# IR_Sensor.net
KiCad netlist of a schematic drawn in EAGLE
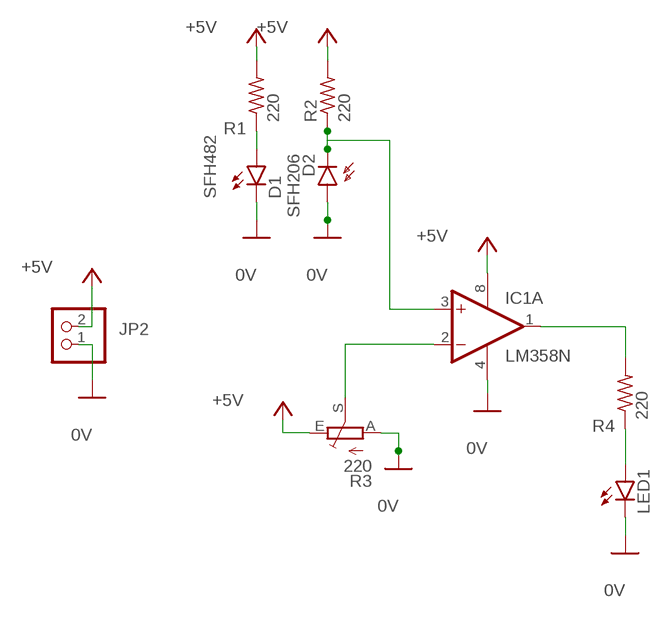
[diagram p0: schematic, sheet 1]

(export (version "E")
  (design (tool "Eeschema 10.0.6"))
  (components
    (comp (ref "D1")
      (value "SFH482")
      (footprint "eagle-import:SFH482")
      (libsource (lib "eagle-import") (part "SFH482"))
    )
    (comp (ref "D2")
      (value "SFH206")
      (footprint "eagle-import:SFH206")
      (fields (field (name "MPN") "SFH206K"))
      (libsource (lib "eagle-import") (part "SFH206"))
    )
    (comp (ref "IC1")
      (value "LM358N")
      (footprint "eagle-import:DIL08")
      (libsource (lib "eagle-import") (part "LM358N"))
    )
    (comp (ref "JP2")
      (value "PINHD-1X2")
      (footprint "eagle-import:1X02")
      (libsource (lib "eagle-import") (part "PINHD-1X2"))
    )
    (comp (ref "LED1")
      (value "LED5MM")
      (footprint "eagle-import:LED5MM")
      (libsource (lib "eagle-import") (part "LED5MM"))
    )
    (comp (ref "R1")
      (value "220")
      (footprint "eagle-import:0207_10")
      (libsource (lib "eagle-import") (part "R-US_0207/10"))
    )
    (comp (ref "R2")
      (value "220")
      (footprint "eagle-import:0207_10")
      (libsource (lib "eagle-import") (part "R-US_0207/10"))
    )
    (comp (ref "R3")
      (value "220")
      (footprint "eagle-import:CA6V")
      (libsource (lib "eagle-import") (part "TRIM_EU-CA6V"))
    )
    (comp (ref "R4")
      (value "220")
      (footprint "eagle-import:0207_10")
      (libsource (lib "eagle-import") (part "R-US_0207/10"))
    )
  )
  (nets
    (net (code "1") (name "+5V") (class "Default")
      (node (ref "IC1") (pin "8") (pinfunction "V+_8") (pintype "power_in"))
      (node (ref "JP2") (pin "2") (pinfunction "2_2") (pintype "passive"))
      (node (ref "R1") (pin "2") (pinfunction "2_2") (pintype "passive"))
      (node (ref "R2") (pin "2") (pinfunction "2_2") (pintype "passive"))
      (node (ref "R3") (pin "E") (pinfunction "E_E") (pintype "passive"))
    )
    (net (code "2") (name "0V") (class "Default")
      (node (ref "D1") (pin "K") (pinfunction "C_K") (pintype "passive"))
      (node (ref "D2") (pin "A") (pinfunction "A_A") (pintype "passive"))
      (node (ref "IC1") (pin "4") (pinfunction "V-_4") (pintype "power_in"))
      (node (ref "JP2") (pin "1") (pinfunction "1_1") (pintype "passive"))
      (node (ref "LED1") (pin "K") (pinfunction "C_K") (pintype "passive"))
      (node (ref "R3") (pin "A") (pinfunction "A_A") (pintype "passive"))
    )
    (net (code "3") (name "Net-(D1-PadA)") (class "Default")
      (node (ref "D1") (pin "A") (pinfunction "A_A") (pintype "passive"))
      (node (ref "R1") (pin "1") (pinfunction "1_1") (pintype "passive"))
    )
    (net (code "4") (name "Net-(D2-C)") (class "Default")
      (node (ref "D2") (pin "K") (pinfunction "C_K") (pintype "passive"))
      (node (ref "IC1") (pin "3") (pinfunction "+IN_3") (pintype "input"))
      (node (ref "R2") (pin "1") (pinfunction "1_1") (pintype "passive"))
    )
    (net (code "5") (name "Net-(IC1A--IN)") (class "Default")
      (node (ref "IC1") (pin "2") (pinfunction "-IN_2") (pintype "input"))
      (node (ref "R3") (pin "S") (pinfunction "S_S") (pintype "passive"))
    )
    (net (code "6") (name "Net-(IC1A-OUT)") (class "Default")
      (node (ref "IC1") (pin "1") (pinfunction "OUT_1") (pintype "output"))
      (node (ref "R4") (pin "2") (pinfunction "2_2") (pintype "passive"))
    )
    (net (code "7") (name "Net-(LED1-PadA)") (class "Default")
      (node (ref "LED1") (pin "A") (pinfunction "A_A") (pintype "passive"))
      (node (ref "R4") (pin "1") (pinfunction "1_1") (pintype "passive"))
    )
  )
)
